# Sheet1.net
KiCad netlist of a schematic drawn in Altium Designer
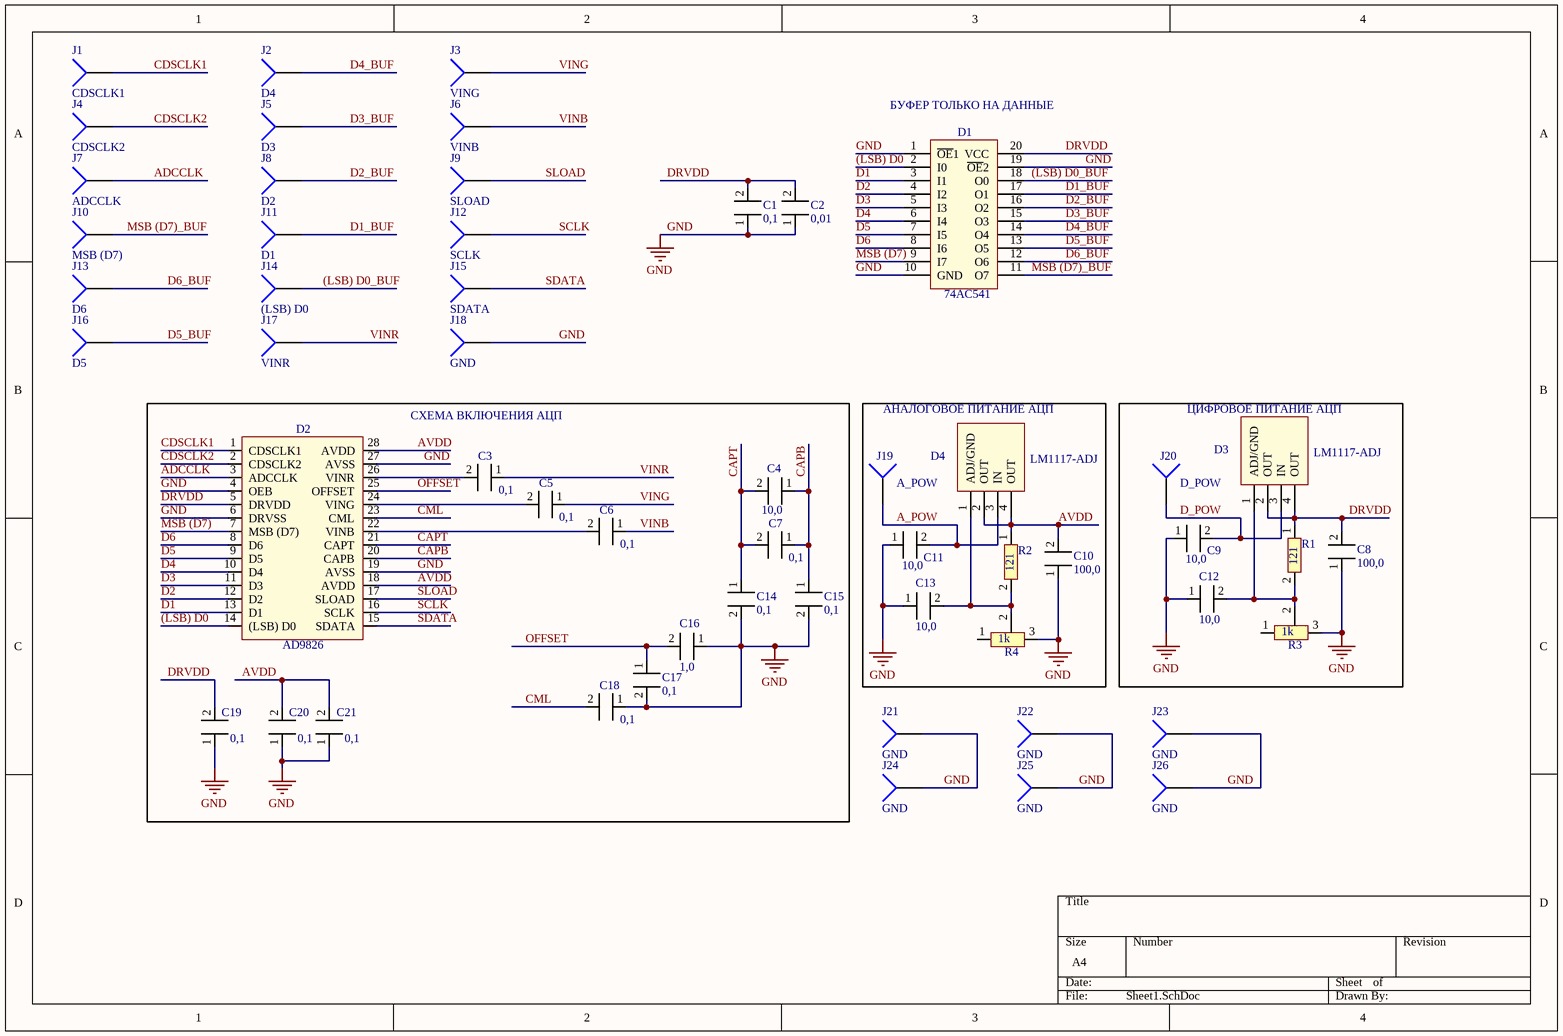
[diagram p0: Sheet1.SchDoc]

(export (version "E")
  (design (tool "Eeschema 10.0.6"))
  (components
    (comp (ref "C1") (value "0,1") (footprint "CAP_SMALL") (libsource (lib "Schlib") (part "CAP_SMALL")))
    (comp (ref "C2") (value "0,01") (footprint "CAP_SMALL") (libsource (lib "Schlib") (part "CAP_SMALL")))
    (comp (ref "C3") (value "0,1") (footprint "CAP_SMALL") (libsource (lib "Schlib") (part "CAP_SMALL")))
    (comp (ref "C4") (value "10,0") (footprint "CAP_SMALL") (libsource (lib "Schlib") (part "CAP_SMALL")))
    (comp (ref "C5") (value "0,1") (footprint "CAP_SMALL") (libsource (lib "Schlib") (part "CAP_SMALL")))
    (comp (ref "C6") (value "0,1") (footprint "CAP_SMALL") (libsource (lib "Schlib") (part "CAP_SMALL")))
    (comp (ref "C7") (value "0,1") (footprint "CAP_SMALL") (libsource (lib "Schlib") (part "CAP_SMALL")))
    (comp (ref "C8") (value "100,0") (footprint "Cap_BIG") (libsource (lib "Schlib") (part "CAP_BIG")))
    (comp (ref "C9") (value "10,0") (footprint "Cap_BIG") (libsource (lib "Schlib") (part "CAP_BIG")))
    (comp (ref "C10") (value "100,0") (footprint "Cap_BIG") (libsource (lib "Schlib") (part "CAP_BIG")))
    (comp (ref "C11") (value "10,0") (footprint "Cap_BIG") (libsource (lib "Schlib") (part "CAP_BIG")))
    (comp (ref "C12") (value "10,0") (footprint "Cap_BIG") (libsource (lib "Schlib") (part "CAP_BIG")))
    (comp (ref "C13") (value "10,0") (footprint "Cap_BIG") (libsource (lib "Schlib") (part "CAP_BIG")))
    (comp (ref "C14") (value "0,1") (footprint "CAP_SMALL") (libsource (lib "Schlib") (part "CAP_SMALL")))
    (comp (ref "C15") (value "0,1") (footprint "CAP_SMALL") (libsource (lib "Schlib") (part "CAP_SMALL")))
    (comp (ref "C16") (value "1,0") (footprint "CAP_SMALL") (libsource (lib "Schlib") (part "CAP_SMALL")))
    (comp (ref "C17") (value "0,1") (footprint "CAP_SMALL") (libsource (lib "Schlib") (part "CAP_SMALL")))
    (comp (ref "C18") (value "0,1") (footprint "CAP_SMALL") (libsource (lib "Schlib") (part "CAP_SMALL")))
    (comp (ref "C19") (value "0,1") (footprint "CAP_SMALL") (libsource (lib "Schlib") (part "CAP_SMALL")))
    (comp (ref "C20") (value "0,1") (footprint "CAP_SMALL") (libsource (lib "Schlib") (part "CAP_SMALL")))
    (comp (ref "C21") (value "0,1") (footprint "CAP_SMALL") (libsource (lib "Schlib") (part "CAP_SMALL")))
    (comp (ref "D1") (value "74AC541") (footprint "20S_M") (libsource (lib "Schlib") (part "74AC541")))
    (comp (ref "D2") (value "AD9826") (footprint "SSOP-28") (libsource (lib "Schlib") (part "AD9826")))
    (comp (ref "D3")
      (value "LM1117-ADJ")
      (footprint "SOT230P700X180-4N")
      (libsource (lib "Schlib") (part "LM1117-ADJ"))
    )
    (comp (ref "D4")
      (value "LM1117-ADJ")
      (footprint "SOT230P700X180-4N")
      (libsource (lib "Schlib") (part "LM1117-ADJ"))
    )
    (comp (ref "J1")
      (value "CDSCLK1")
      (footprint "PIN1")
      (description "Socket")
      (fields (field (name "PUBLISHER") "Altium Limited"))
      (libsource (lib "Miscellaneous Connectors") (part "Socket"))
    )
    (comp (ref "J2")
      (value "D4")
      (footprint "PIN1")
      (description "Socket")
      (fields (field (name "PUBLISHER") "Altium Limited"))
      (libsource (lib "Miscellaneous Connectors") (part "Socket"))
    )
    (comp (ref "J3")
      (value "VING")
      (footprint "PIN1")
      (description "Socket")
      (fields (field (name "PUBLISHER") "Altium Limited"))
      (libsource (lib "Miscellaneous Connectors") (part "Socket"))
    )
    (comp (ref "J4")
      (value "CDSCLK2")
      (footprint "PIN1")
      (description "Socket")
      (fields (field (name "PUBLISHER") "Altium Limited"))
      (libsource (lib "Miscellaneous Connectors") (part "Socket"))
    )
    (comp (ref "J5")
      (value "D3")
      (footprint "PIN1")
      (description "Socket")
      (fields (field (name "PUBLISHER") "Altium Limited"))
      (libsource (lib "Miscellaneous Connectors") (part "Socket"))
    )
    (comp (ref "J6")
      (value "VINB")
      (footprint "PIN1")
      (description "Socket")
      (fields (field (name "PUBLISHER") "Altium Limited"))
      (libsource (lib "Miscellaneous Connectors") (part "Socket"))
    )
    (comp (ref "J7")
      (value "ADCCLK")
      (footprint "PIN1")
      (description "Socket")
      (fields (field (name "PUBLISHER") "Altium Limited"))
      (libsource (lib "Miscellaneous Connectors") (part "Socket"))
    )
    (comp (ref "J8")
      (value "D2")
      (footprint "PIN1")
      (description "Socket")
      (fields (field (name "PUBLISHER") "Altium Limited"))
      (libsource (lib "Miscellaneous Connectors") (part "Socket"))
    )
    (comp (ref "J9")
      (value "SLOAD")
      (footprint "PIN1")
      (description "Socket")
      (fields (field (name "PUBLISHER") "Altium Limited"))
      (libsource (lib "Miscellaneous Connectors") (part "Socket"))
    )
    (comp (ref "J10")
      (value "MSB (D7)")
      (footprint "PIN1")
      (description "Socket")
      (fields (field (name "PUBLISHER") "Altium Limited"))
      (libsource (lib "Miscellaneous Connectors") (part "Socket"))
    )
    (comp (ref "J11")
      (value "D1")
      (footprint "PIN1")
      (description "Socket")
      (fields (field (name "PUBLISHER") "Altium Limited"))
      (libsource (lib "Miscellaneous Connectors") (part "Socket"))
    )
    (comp (ref "J12")
      (value "SCLK")
      (footprint "PIN1")
      (description "Socket")
      (fields (field (name "PUBLISHER") "Altium Limited"))
      (libsource (lib "Miscellaneous Connectors") (part "Socket"))
    )
    (comp (ref "J13")
      (value "D6")
      (footprint "PIN1")
      (description "Socket")
      (fields (field (name "PUBLISHER") "Altium Limited"))
      (libsource (lib "Miscellaneous Connectors") (part "Socket"))
    )
    (comp (ref "J14")
      (value "(LSB) D0")
      (footprint "PIN1")
      (description "Socket")
      (fields (field (name "PUBLISHER") "Altium Limited"))
      (libsource (lib "Miscellaneous Connectors") (part "Socket"))
    )
    (comp (ref "J15")
      (value "SDATA")
      (footprint "PIN1")
      (description "Socket")
      (fields (field (name "PUBLISHER") "Altium Limited"))
      (libsource (lib "Miscellaneous Connectors") (part "Socket"))
    )
    (comp (ref "J16")
      (value "D5")
      (footprint "PIN1")
      (description "Socket")
      (fields (field (name "PUBLISHER") "Altium Limited"))
      (libsource (lib "Miscellaneous Connectors") (part "Socket"))
    )
    (comp (ref "J17")
      (value "VINR")
      (footprint "PIN1")
      (description "Socket")
      (fields (field (name "PUBLISHER") "Altium Limited"))
      (libsource (lib "Miscellaneous Connectors") (part "Socket"))
    )
    (comp (ref "J18")
      (value "GND")
      (footprint "PIN1")
      (description "Socket")
      (fields (field (name "PUBLISHER") "Altium Limited"))
      (libsource (lib "Miscellaneous Connectors") (part "Socket"))
    )
    (comp (ref "J19")
      (value "A_POW")
      (footprint "PIN1")
      (description "Socket")
      (fields (field (name "PUBLISHER") "Altium Limited"))
      (libsource (lib "Miscellaneous Connectors") (part "Socket"))
    )
    (comp (ref "J20")
      (value "D_POW")
      (footprint "PIN1")
      (description "Socket")
      (fields (field (name "PUBLISHER") "Altium Limited"))
      (libsource (lib "Miscellaneous Connectors") (part "Socket"))
    )
    (comp (ref "J21")
      (value "GND")
      (footprint "PIN1")
      (description "Socket")
      (fields (field (name "PUBLISHER") "Altium Limited"))
      (libsource (lib "Miscellaneous Connectors") (part "Socket"))
    )
    (comp (ref "J22")
      (value "GND")
      (footprint "PIN1")
      (description "Socket")
      (fields (field (name "PUBLISHER") "Altium Limited"))
      (libsource (lib "Miscellaneous Connectors") (part "Socket"))
    )
    (comp (ref "J23")
      (value "GND")
      (footprint "PIN1")
      (description "Socket")
      (fields (field (name "PUBLISHER") "Altium Limited"))
      (libsource (lib "Miscellaneous Connectors") (part "Socket"))
    )
    (comp (ref "J24")
      (value "GND")
      (footprint "PIN1")
      (description "Socket")
      (fields (field (name "PUBLISHER") "Altium Limited"))
      (libsource (lib "Miscellaneous Connectors") (part "Socket"))
    )
    (comp (ref "J25")
      (value "GND")
      (footprint "PIN1")
      (description "Socket")
      (fields (field (name "PUBLISHER") "Altium Limited"))
      (libsource (lib "Miscellaneous Connectors") (part "Socket"))
    )
    (comp (ref "J26")
      (value "GND")
      (footprint "PIN1")
      (description "Socket")
      (fields (field (name "PUBLISHER") "Altium Limited"))
      (libsource (lib "Miscellaneous Connectors") (part "Socket"))
    )
    (comp (ref "R1") (value "121") (footprint "RES") (libsource (lib "Schlib") (part "RES")))
    (comp (ref "R2") (value "121") (footprint "RES") (libsource (lib "Schlib") (part "RES")))
    (comp (ref "R3") (value "1k") (footprint "PODSR_RES") (libsource (lib "Schlib") (part "RES_PODSTR")))
    (comp (ref "R4") (value "1k") (footprint "PODSR_RES") (libsource (lib "Schlib") (part "RES_PODSTR")))
  )
  (nets
    (net (code "1") (name "/(LSB) D0") (class "Default")
      (node (ref "D1") (pin "2") (pinfunction "I0_2") (pintype "passive"))
      (node (ref "D2") (pin "14") (pinfunction "(LSB)_D0_14") (pintype "passive"))
    )
    (net (code "2") (name "/(LSB) D0_BUF") (class "Default")
      (node (ref "D1") (pin "18") (pinfunction "O0_18") (pintype "passive"))
      (node (ref "J14") (pin "1") (pinfunction "1_1") (pintype "passive"))
    )
    (net (code "3") (name "/ADCCLK") (class "Default")
      (node (ref "D2") (pin "3") (pinfunction "ADCCLK_3") (pintype "passive"))
      (node (ref "J7") (pin "1") (pinfunction "1_1") (pintype "passive"))
    )
    (net (code "4") (name "/AVDD") (class "Default")
      (node (ref "C10") (pin "2") (pinfunction "2_2") (pintype "passive"))
      (node (ref "C20") (pin "2") (pinfunction "2_2") (pintype "passive"))
      (node (ref "C21") (pin "2") (pinfunction "2_2") (pintype "passive"))
      (node (ref "D2") (pin "18") (pinfunction "AVDD_18") (pintype "passive"))
      (node (ref "D2") (pin "28") (pinfunction "AVDD_28") (pintype "passive"))
      (node (ref "D4") (pin "2") (pinfunction "OUT_2") (pintype "passive"))
      (node (ref "D4") (pin "4") (pinfunction "OUT_4") (pintype "passive"))
      (node (ref "R2") (pin "1") (pinfunction "1_1") (pintype "passive"))
    )
    (net (code "5") (name "/A_POW") (class "Default")
      (node (ref "C11") (pin "2") (pinfunction "2_2") (pintype "passive"))
      (node (ref "D4") (pin "3") (pinfunction "IN_3") (pintype "passive"))
      (node (ref "J19") (pin "1") (pinfunction "1_1") (pintype "passive"))
    )
    (net (code "6") (name "/CAPB") (class "Default")
      (node (ref "C15") (pin "1") (pinfunction "1_1") (pintype "passive"))
      (node (ref "C4") (pin "1") (pinfunction "1_1") (pintype "passive"))
      (node (ref "C7") (pin "1") (pinfunction "1_1") (pintype "passive"))
      (node (ref "D2") (pin "20") (pinfunction "CAPB_20") (pintype "passive"))
    )
    (net (code "7") (name "/CAPT") (class "Default")
      (node (ref "C14") (pin "1") (pinfunction "1_1") (pintype "passive"))
      (node (ref "C4") (pin "2") (pinfunction "2_2") (pintype "passive"))
      (node (ref "C7") (pin "2") (pinfunction "2_2") (pintype "passive"))
      (node (ref "D2") (pin "21") (pinfunction "CAPT_21") (pintype "passive"))
    )
    (net (code "8") (name "/CDSCLK1") (class "Default")
      (node (ref "D2") (pin "1") (pinfunction "CDSCLK1_1") (pintype "passive"))
      (node (ref "J1") (pin "1") (pinfunction "1_1") (pintype "passive"))
    )
    (net (code "9") (name "/CDSCLK2") (class "Default")
      (node (ref "D2") (pin "2") (pinfunction "CDSCLK2_2") (pintype "passive"))
      (node (ref "J4") (pin "1") (pinfunction "1_1") (pintype "passive"))
    )
    (net (code "10") (name "/CML") (class "Default")
      (node (ref "C18") (pin "2") (pinfunction "2_2") (pintype "passive"))
      (node (ref "D2") (pin "23") (pinfunction "CML_23") (pintype "passive"))
    )
    (net (code "11") (name "/D1") (class "Default")
      (node (ref "D1") (pin "3") (pinfunction "I1_3") (pintype "passive"))
      (node (ref "D2") (pin "13") (pinfunction "D1_13") (pintype "passive"))
    )
    (net (code "12") (name "/D1_BUF") (class "Default")
      (node (ref "D1") (pin "17") (pinfunction "O1_17") (pintype "passive"))
      (node (ref "J11") (pin "1") (pinfunction "1_1") (pintype "passive"))
    )
    (net (code "13") (name "/D2") (class "Default")
      (node (ref "D1") (pin "4") (pinfunction "I2_4") (pintype "passive"))
      (node (ref "D2") (pin "12") (pinfunction "D2_12") (pintype "passive"))
    )
    (net (code "14") (name "/D2_BUF") (class "Default")
      (node (ref "D1") (pin "16") (pinfunction "O2_16") (pintype "passive"))
      (node (ref "J8") (pin "1") (pinfunction "1_1") (pintype "passive"))
    )
    (net (code "15") (name "/D3") (class "Default")
      (node (ref "D1") (pin "5") (pinfunction "I3_5") (pintype "passive"))
      (node (ref "D2") (pin "11") (pinfunction "D3_11") (pintype "passive"))
    )
    (net (code "16") (name "/D3_BUF") (class "Default")
      (node (ref "D1") (pin "15") (pinfunction "O3_15") (pintype "passive"))
      (node (ref "J5") (pin "1") (pinfunction "1_1") (pintype "passive"))
    )
    (net (code "17") (name "/D4") (class "Default")
      (node (ref "D1") (pin "6") (pinfunction "I4_6") (pintype "passive"))
      (node (ref "D2") (pin "10") (pinfunction "D4_10") (pintype "passive"))
    )
    (net (code "18") (name "/D4_BUF") (class "Default")
      (node (ref "D1") (pin "14") (pinfunction "O4_14") (pintype "passive"))
      (node (ref "J2") (pin "1") (pinfunction "1_1") (pintype "passive"))
    )
    (net (code "19") (name "/D5") (class "Default")
      (node (ref "D1") (pin "7") (pinfunction "I5_7") (pintype "passive"))
      (node (ref "D2") (pin "9") (pinfunction "D5_9") (pintype "passive"))
    )
    (net (code "20") (name "/D5_BUF") (class "Default")
      (node (ref "D1") (pin "13") (pinfunction "O5_13") (pintype "passive"))
      (node (ref "J16") (pin "1") (pinfunction "1_1") (pintype "passive"))
    )
    (net (code "21") (name "/D6") (class "Default")
      (node (ref "D1") (pin "8") (pinfunction "I6_8") (pintype "passive"))
      (node (ref "D2") (pin "8") (pinfunction "D6_8") (pintype "passive"))
    )
    (net (code "22") (name "/D6_BUF") (class "Default")
      (node (ref "D1") (pin "12") (pinfunction "O6_12") (pintype "passive"))
      (node (ref "J13") (pin "1") (pinfunction "1_1") (pintype "passive"))
    )
    (net (code "23") (name "/DRVDD") (class "Default")
      (node (ref "C1") (pin "2") (pinfunction "2_2") (pintype "passive"))
      (node (ref "C19") (pin "2") (pinfunction "2_2") (pintype "passive"))
      (node (ref "C2") (pin "2") (pinfunction "2_2") (pintype "passive"))
      (node (ref "C8") (pin "2") (pinfunction "2_2") (pintype "passive"))
      (node (ref "D1") (pin "20") (pinfunction "VCC_20") (pintype "passive"))
      (node (ref "D2") (pin "5") (pinfunction "DRVDD_5") (pintype "passive"))
      (node (ref "D3") (pin "2") (pinfunction "OUT_2") (pintype "passive"))
      (node (ref "D3") (pin "4") (pinfunction "OUT_4") (pintype "passive"))
      (node (ref "R1") (pin "1") (pinfunction "1_1") (pintype "passive"))
    )
    (net (code "24") (name "/D_POW") (class "Default")
      (node (ref "C9") (pin "2") (pinfunction "2_2") (pintype "passive"))
      (node (ref "D3") (pin "3") (pinfunction "IN_3") (pintype "passive"))
      (node (ref "J20") (pin "1") (pinfunction "1_1") (pintype "passive"))
    )
    (net (code "25") (name "/MSB (D7)") (class "Default")
      (node (ref "D1") (pin "9") (pinfunction "I7_9") (pintype "passive"))
      (node (ref "D2") (pin "7") (pinfunction "MSB_(D7)_7") (pintype "passive"))
    )
    (net (code "26") (name "/MSB (D7)_BUF") (class "Default")
      (node (ref "D1") (pin "11") (pinfunction "O7_11") (pintype "passive"))
      (node (ref "J10") (pin "1") (pinfunction "1_1") (pintype "passive"))
    )
    (net (code "27") (name "/OFFSET") (class "Default")
      (node (ref "C16") (pin "2") (pinfunction "2_2") (pintype "passive"))
      (node (ref "C17") (pin "1") (pinfunction "1_1") (pintype "passive"))
      (node (ref "D2") (pin "25") (pinfunction "OFFSET_25") (pintype "passive"))
    )
    (net (code "28") (name "/SCLK") (class "Default")
      (node (ref "D2") (pin "16") (pinfunction "SCLK_16") (pintype "passive"))
      (node (ref "J12") (pin "1") (pinfunction "1_1") (pintype "passive"))
    )
    (net (code "29") (name "/SDATA") (class "Default")
      (node (ref "D2") (pin "15") (pinfunction "SDATA_15") (pintype "passive"))
      (node (ref "J15") (pin "1") (pinfunction "1_1") (pintype "passive"))
    )
    (net (code "30") (name "/SLOAD") (class "Default")
      (node (ref "D2") (pin "17") (pinfunction "SLOAD_17") (pintype "passive"))
      (node (ref "J9") (pin "1") (pinfunction "1_1") (pintype "passive"))
    )
    (net (code "31") (name "/VINB") (class "Default")
      (node (ref "C6") (pin "1") (pinfunction "1_1") (pintype "passive"))
      (node (ref "J6") (pin "1") (pinfunction "1_1") (pintype "passive"))
    )
    (net (code "32") (name "/VING") (class "Default")
      (node (ref "C5") (pin "1") (pinfunction "1_1") (pintype "passive"))
      (node (ref "J3") (pin "1") (pinfunction "1_1") (pintype "passive"))
    )
    (net (code "33") (name "/VINR") (class "Default")
      (node (ref "C3") (pin "1") (pinfunction "1_1") (pintype "passive"))
      (node (ref "J17") (pin "1") (pinfunction "1_1") (pintype "passive"))
    )
    (net (code "34") (name "GND") (class "Default")
      (node (ref "C1") (pin "1") (pinfunction "1_1") (pintype "passive"))
      (node (ref "C10") (pin "1") (pinfunction "1_1") (pintype "passive"))
      (node (ref "C11") (pin "1") (pinfunction "1_1") (pintype "passive"))
      (node (ref "C12") (pin "1") (pinfunction "1_1") (pintype "passive"))
      (node (ref "C13") (pin "1") (pinfunction "1_1") (pintype "passive"))
      (node (ref "C14") (pin "2") (pinfunction "2_2") (pintype "passive"))
      (node (ref "C15") (pin "2") (pinfunction "2_2") (pintype "passive"))
      (node (ref "C16") (pin "1") (pinfunction "1_1") (pintype "passive"))
      (node (ref "C17") (pin "2") (pinfunction "2_2") (pintype "passive"))
      (node (ref "C18") (pin "1") (pinfunction "1_1") (pintype "passive"))
      (node (ref "C19") (pin "1") (pinfunction "1_1") (pintype "passive"))
      (node (ref "C2") (pin "1") (pinfunction "1_1") (pintype "passive"))
      (node (ref "C20") (pin "1") (pinfunction "1_1") (pintype "passive"))
      (node (ref "C21") (pin "1") (pinfunction "1_1") (pintype "passive"))
      (node (ref "C8") (pin "1") (pinfunction "1_1") (pintype "passive"))
      (node (ref "C9") (pin "1") (pinfunction "1_1") (pintype "passive"))
      (node (ref "D1") (pin "1") (pinfunction "~{OE}1_1") (pintype "passive"))
      (node (ref "D1") (pin "10") (pinfunction "GND_10") (pintype "passive"))
      (node (ref "D1") (pin "19") (pinfunction "~{OE}2_19") (pintype "passive"))
      (node (ref "D2") (pin "19") (pinfunction "AVSS_19") (pintype "passive"))
      (node (ref "D2") (pin "27") (pinfunction "AVSS_27") (pintype "passive"))
      (node (ref "D2") (pin "4") (pinfunction "OEB_4") (pintype "passive"))
      (node (ref "D2") (pin "6") (pinfunction "DRVSS_6") (pintype "passive"))
      (node (ref "J18") (pin "1") (pinfunction "1_1") (pintype "passive"))
      (node (ref "J21") (pin "1") (pinfunction "1_1") (pintype "passive"))
      (node (ref "J22") (pin "1") (pinfunction "1_1") (pintype "passive"))
      (node (ref "J23") (pin "1") (pinfunction "1_1") (pintype "passive"))
      (node (ref "J24") (pin "1") (pinfunction "1_1") (pintype "passive"))
      (node (ref "J25") (pin "1") (pinfunction "1_1") (pintype "passive"))
      (node (ref "J26") (pin "1") (pinfunction "1_1") (pintype "passive"))
      (node (ref "R3") (pin "3") (pinfunction "3_3") (pintype "passive"))
      (node (ref "R4") (pin "3") (pinfunction "3_3") (pintype "passive"))
    )
    (net (code "35") (name "Net-(D2-VINB)") (class "Default")
      (node (ref "C6") (pin "2") (pinfunction "2_2") (pintype "passive"))
      (node (ref "D2") (pin "22") (pinfunction "VINB_22") (pintype "passive"))
    )
    (net (code "36") (name "Net-(D2-VING)") (class "Default")
      (node (ref "C5") (pin "2") (pinfunction "2_2") (pintype "passive"))
      (node (ref "D2") (pin "24") (pinfunction "VING_24") (pintype "passive"))
    )
    (net (code "37") (name "Net-(D2-VINR)") (class "Default")
      (node (ref "C3") (pin "2") (pinfunction "2_2") (pintype "passive"))
      (node (ref "D2") (pin "26") (pinfunction "VINR_26") (pintype "passive"))
    )
    (net (code "38") (name "Net-(D3-ADJ{slash}GND)") (class "Default")
      (node (ref "C12") (pin "2") (pinfunction "2_2") (pintype "passive"))
      (node (ref "D3") (pin "1") (pinfunction "ADJ/GND_1") (pintype "passive"))
      (node (ref "R1") (pin "2") (pinfunction "2_2") (pintype "passive"))
      (node (ref "R3") (pin "2") (pinfunction "2_2") (pintype "passive"))
    )
    (net (code "39") (name "Net-(D4-ADJ{slash}GND)") (class "Default")
      (node (ref "C13") (pin "2") (pinfunction "2_2") (pintype "passive"))
      (node (ref "D4") (pin "1") (pinfunction "ADJ/GND_1") (pintype "passive"))
      (node (ref "R2") (pin "2") (pinfunction "2_2") (pintype "passive"))
      (node (ref "R4") (pin "2") (pinfunction "2_2") (pintype "passive"))
    )
    (net (code "40") (name "unconnected-(R3-Pad1)") (class "Default")
      (node (ref "R3") (pin "1") (pinfunction "1_1") (pintype "passive"))
    )
    (net (code "41") (name "unconnected-(R4-Pad1)") (class "Default")
      (node (ref "R4") (pin "1") (pinfunction "1_1") (pintype "passive"))
    )
  )
)
